# Pool_Interface_FEATHER-ESP8266.net
KiCad netlist of a schematic drawn in EAGLE
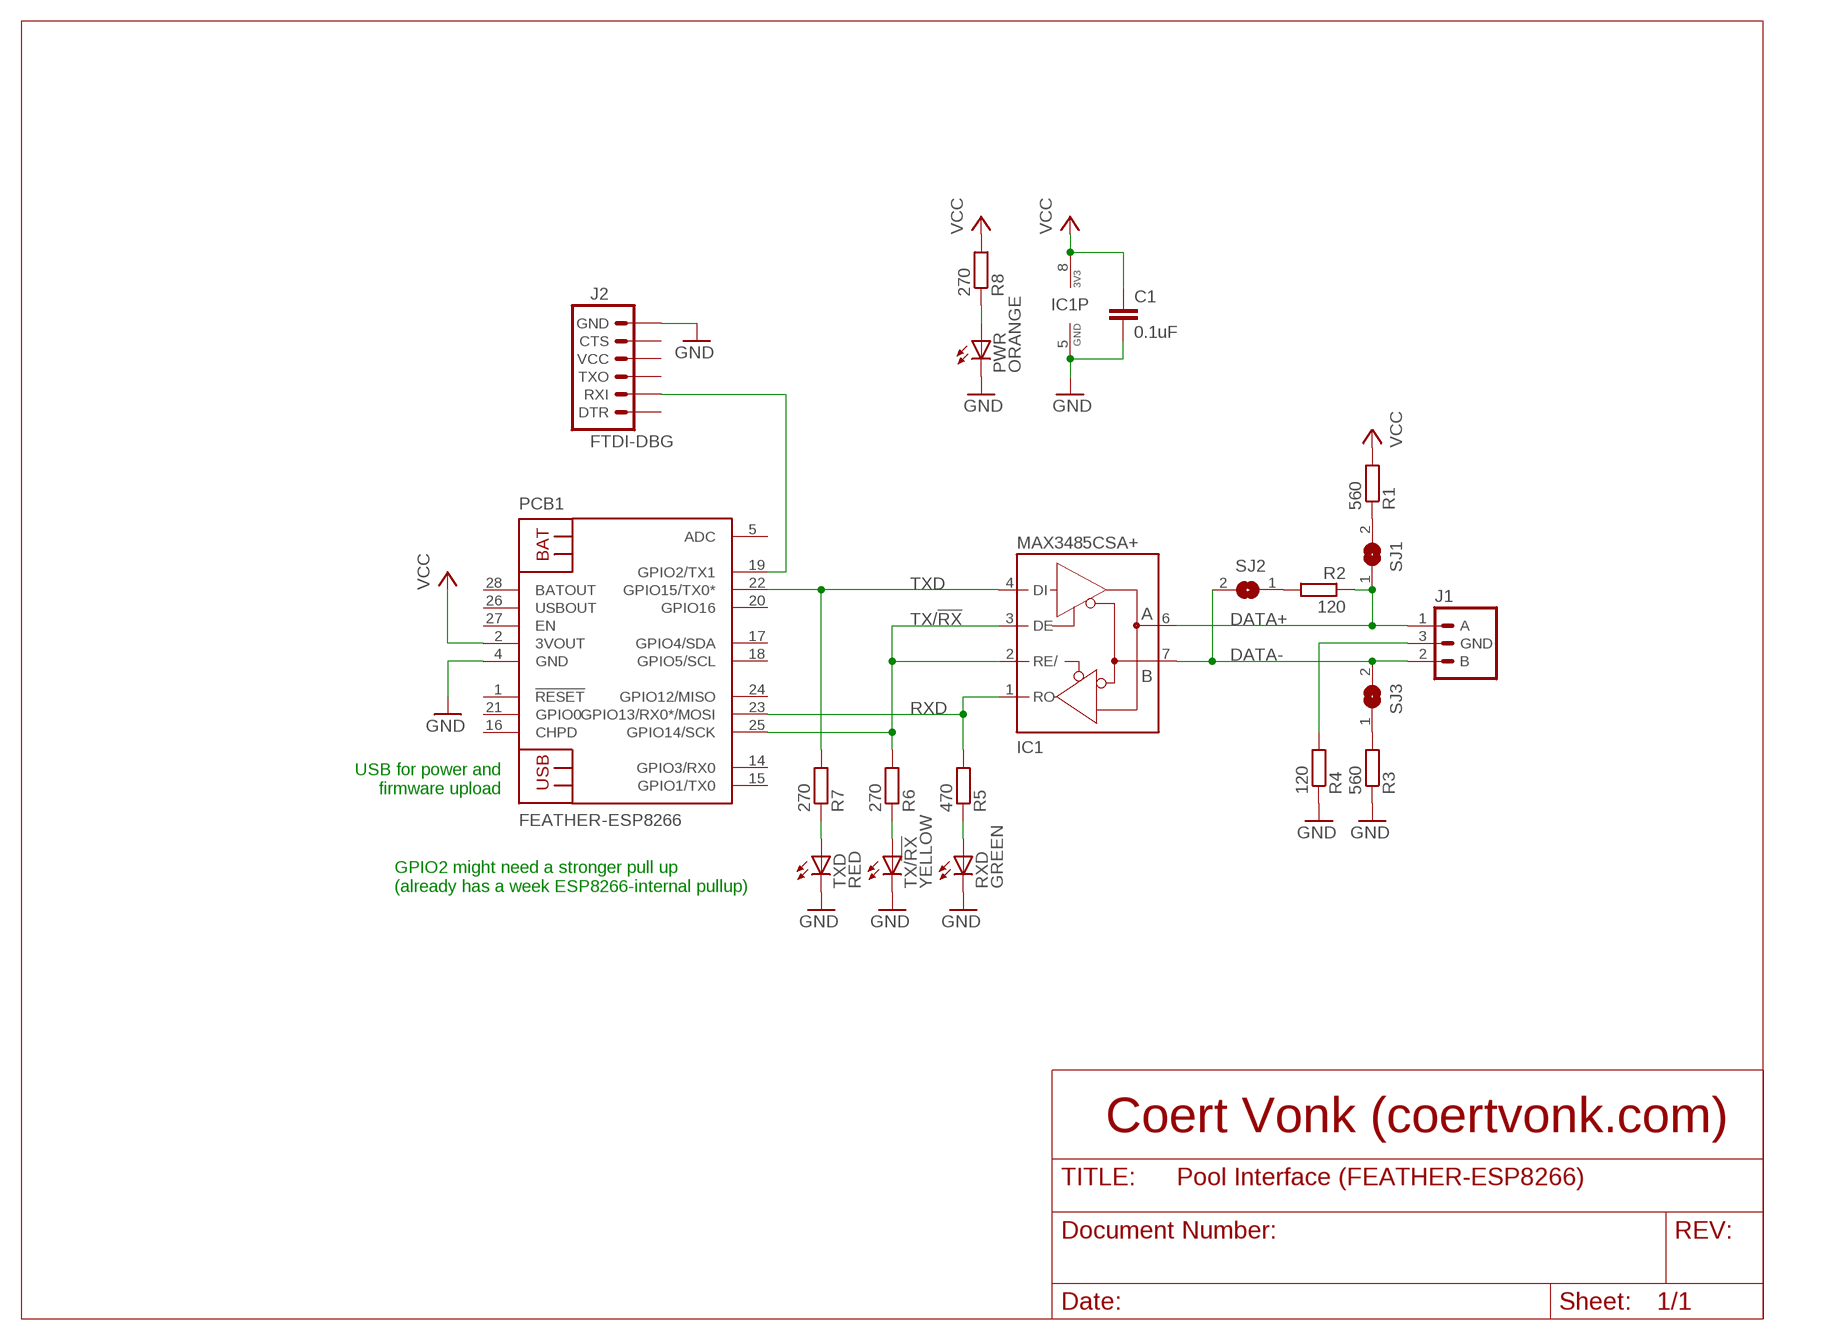
[diagram p0: schematic, sheet 1]

(export (version "E")
  (design (tool "Eeschema 10.0.6"))
  (components
    (comp (ref "C1")
      (value "0.1uF")
      (footprint "eagle-import:C0805K")
      (libsource (lib "eagle-import") (part "C-EUC0805K"))
    )
    (comp (ref "IC1")
      (value "MAX3485CSA+")
      (footprint "eagle-import:SO08")
      (fields (field (name "MF") "MAXIM") (field (name "MPN") "MAX481CSA"))
      (libsource (lib "eagle-import") (part "MAX3485CSA+"))
    )
    (comp (ref "J1")
      (value "RS485-CONSCREW")
      (footprint "eagle-import:SCREWTERMINAL-3.5MM-3")
      (libsource (lib "eagle-import") (part "RS485-CONSCREW"))
    )
    (comp (ref "J2")
      (value "FTDI-DBG")
      (footprint "eagle-import:1X06_LONGPADS")
      (libsource (lib "eagle-import") (part "ARDUINO_SERIAL_PROGRAMLONGPADS"))
    )
    (comp (ref "PCB1")
      (value "FEATHER-ESP8266")
      (footprint "eagle-import:FEATHER-ESP8266")
      (libsource (lib "eagle-import") (part "FEATHER-ESP8266"))
    )
    (comp (ref "PWR")
      (value "ORANGE")
      (footprint "eagle-import:SML0805")
      (libsource (lib "eagle-import") (part "LEDSML0805"))
    )
    (comp (ref "R1")
      (value "560")
      (footprint "eagle-import:R0805")
      (libsource (lib "eagle-import") (part "R-EU_R0805"))
    )
    (comp (ref "R2")
      (value "120")
      (footprint "eagle-import:R0805")
      (libsource (lib "eagle-import") (part "R-EU_R0805"))
    )
    (comp (ref "R3")
      (value "560")
      (footprint "eagle-import:R0805")
      (libsource (lib "eagle-import") (part "R-EU_R0805"))
    )
    (comp (ref "R4")
      (value "120")
      (footprint "eagle-import:R0805")
      (libsource (lib "eagle-import") (part "R-EU_R0805"))
    )
    (comp (ref "R5")
      (value "470")
      (footprint "eagle-import:R0805")
      (libsource (lib "eagle-import") (part "R-EU_R0805"))
    )
    (comp (ref "R6")
      (value "270")
      (footprint "eagle-import:R0805")
      (libsource (lib "eagle-import") (part "R-EU_R0805"))
    )
    (comp (ref "R7")
      (value "270")
      (footprint "eagle-import:R0805")
      (libsource (lib "eagle-import") (part "R-EU_R0805"))
    )
    (comp (ref "R8")
      (value "270")
      (footprint "eagle-import:R0805")
      (libsource (lib "eagle-import") (part "R-EU_R0805"))
    )
    (comp (ref "RXD")
      (value "GREEN")
      (footprint "eagle-import:SML0805")
      (libsource (lib "eagle-import") (part "LEDSML0805"))
    )
    (comp (ref "SJ1") (value "SJ") (footprint "eagle-import:SJ") (libsource (lib "eagle-import") (part "SJ")))
    (comp (ref "SJ2") (value "SJ") (footprint "eagle-import:SJ") (libsource (lib "eagle-import") (part "SJ")))
    (comp (ref "SJ3") (value "SJ") (footprint "eagle-import:SJ") (libsource (lib "eagle-import") (part "SJ")))
    (comp (ref "TX/!RX")
      (value "YELLOW")
      (footprint "eagle-import:SML0805")
      (libsource (lib "eagle-import") (part "LEDSML0805"))
    )
    (comp (ref "TXD")
      (value "RED")
      (footprint "eagle-import:SML0805")
      (libsource (lib "eagle-import") (part "LEDSML0805"))
    )
  )
  (nets
    (net (code "1") (name "/BATOUT") (class "Default")
      (node (ref "PCB1") (pin "28") (pinfunction "BATOUT_28") (pintype "power_in"))
    )
    (net (code "2") (name "/DATA+") (class "Default")
      (node (ref "IC1") (pin "6") (pinfunction "A_6") (pintype "passive"))
      (node (ref "J1") (pin "1") (pinfunction "A_1") (pintype "passive"))
      (node (ref "R2") (pin "1") (pinfunction "1_1") (pintype "passive"))
      (node (ref "SJ1") (pin "1") (pinfunction "1_1") (pintype "passive"))
    )
    (net (code "3") (name "/DATA-") (class "Default")
      (node (ref "IC1") (pin "7") (pinfunction "B_7") (pintype "passive"))
      (node (ref "J1") (pin "2") (pinfunction "B_2") (pintype "passive"))
      (node (ref "SJ2") (pin "2") (pinfunction "2_2") (pintype "passive"))
      (node (ref "SJ3") (pin "2") (pinfunction "2_2") (pintype "passive"))
    )
    (net (code "4") (name "/RXD") (class "Default")
      (node (ref "IC1") (pin "1") (pinfunction "RO_1") (pintype "output"))
      (node (ref "PCB1") (pin "23") (pinfunction "GPIO13/RX0*/MOSI_23") (pintype "bidirectional"))
      (node (ref "R5") (pin "2") (pinfunction "2_2") (pintype "passive"))
    )
    (net (code "5") (name "/TXD") (class "Default")
      (node (ref "IC1") (pin "4") (pinfunction "DI_4") (pintype "input"))
      (node (ref "PCB1") (pin "22") (pinfunction "GPIO15/TX0*_22") (pintype "bidirectional"))
      (node (ref "R7") (pin "2") (pinfunction "2_2") (pintype "passive"))
    )
    (net (code "6") (name "/TX{slash}~{RX}") (class "Default")
      (node (ref "IC1") (pin "2") (pinfunction "RE/_2") (pintype "input"))
      (node (ref "IC1") (pin "3") (pinfunction "DE_3") (pintype "input"))
      (node (ref "PCB1") (pin "25") (pinfunction "GPIO14/SCK_25") (pintype "bidirectional"))
      (node (ref "R6") (pin "2") (pinfunction "2_2") (pintype "passive"))
    )
    (net (code "7") (name "/USBOUT") (class "Default")
      (node (ref "PCB1") (pin "26") (pinfunction "USBOUT_26") (pintype "power_in"))
    )
    (net (code "8") (name "GND") (class "Default")
      (node (ref "C1") (pin "2") (pinfunction "2_2") (pintype "passive"))
      (node (ref "IC1") (pin "5") (pinfunction "GND_5") (pintype "power_in"))
      (node (ref "J2") (pin "6") (pinfunction "GND_6") (pintype "passive"))
      (node (ref "PCB1") (pin "4") (pinfunction "GND_4") (pintype "power_in"))
      (node (ref "PWR") (pin "C") (pinfunction "C_C") (pintype "passive"))
      (node (ref "R3") (pin "1") (pinfunction "1_1") (pintype "passive"))
      (node (ref "R4") (pin "1") (pinfunction "1_1") (pintype "passive"))
      (node (ref "RXD") (pin "C") (pinfunction "C_C") (pintype "passive"))
      (node (ref "TX/!RX") (pin "C") (pinfunction "C_C") (pintype "passive"))
      (node (ref "TXD") (pin "C") (pinfunction "C_C") (pintype "passive"))
    )
    (net (code "9") (name "Net-(J1-GND)") (class "Default")
      (node (ref "J1") (pin "3") (pinfunction "GND_3") (pintype "passive"))
      (node (ref "R4") (pin "2") (pinfunction "2_2") (pintype "passive"))
    )
    (net (code "10") (name "Net-(J2-RXI)") (class "Default")
      (node (ref "J2") (pin "2") (pinfunction "RXI_2") (pintype "passive"))
      (node (ref "PCB1") (pin "19") (pinfunction "GPIO2/TX1_19") (pintype "bidirectional"))
    )
    (net (code "11") (name "Net-(PWR-PadA)") (class "Default")
      (node (ref "PWR") (pin "A") (pinfunction "A_A") (pintype "passive"))
      (node (ref "R8") (pin "1") (pinfunction "1_1") (pintype "passive"))
    )
    (net (code "12") (name "Net-(R1-Pad1)") (class "Default")
      (node (ref "R1") (pin "1") (pinfunction "1_1") (pintype "passive"))
      (node (ref "SJ1") (pin "2") (pinfunction "2_2") (pintype "passive"))
    )
    (net (code "13") (name "Net-(R2-Pad2)") (class "Default")
      (node (ref "R2") (pin "2") (pinfunction "2_2") (pintype "passive"))
      (node (ref "SJ2") (pin "1") (pinfunction "1_1") (pintype "passive"))
    )
    (net (code "14") (name "Net-(R3-Pad2)") (class "Default")
      (node (ref "R3") (pin "2") (pinfunction "2_2") (pintype "passive"))
      (node (ref "SJ3") (pin "1") (pinfunction "1_1") (pintype "passive"))
    )
    (net (code "15") (name "Net-(R5-Pad1)") (class "Default")
      (node (ref "R5") (pin "1") (pinfunction "1_1") (pintype "passive"))
      (node (ref "RXD") (pin "A") (pinfunction "A_A") (pintype "passive"))
    )
    (net (code "16") (name "Net-(R6-Pad1)") (class "Default")
      (node (ref "R6") (pin "1") (pinfunction "1_1") (pintype "passive"))
      (node (ref "TX/!RX") (pin "A") (pinfunction "A_A") (pintype "passive"))
    )
    (net (code "17") (name "Net-(R7-Pad1)") (class "Default")
      (node (ref "R7") (pin "1") (pinfunction "1_1") (pintype "passive"))
      (node (ref "TXD") (pin "A") (pinfunction "A_A") (pintype "passive"))
    )
    (net (code "18") (name "VCC") (class "Default")
      (node (ref "C1") (pin "1") (pinfunction "1_1") (pintype "passive"))
      (node (ref "IC1") (pin "8") (pinfunction "5V_8") (pintype "power_in"))
      (node (ref "PCB1") (pin "2") (pinfunction "3VOUT_2") (pintype "power_in"))
      (node (ref "R1") (pin "2") (pinfunction "2_2") (pintype "passive"))
      (node (ref "R8") (pin "2") (pinfunction "2_2") (pintype "passive"))
    )
    (net (code "19") (name "unconnected-(J2-CTS-Pad5)") (class "Default")
      (node (ref "J2") (pin "5") (pinfunction "CTS_5") (pintype "passive"))
    )
    (net (code "20") (name "unconnected-(J2-DTR-Pad1)") (class "Default")
      (node (ref "J2") (pin "1") (pinfunction "DTR_1") (pintype "passive"))
    )
    (net (code "21") (name "unconnected-(J2-TXO-Pad3)") (class "Default")
      (node (ref "J2") (pin "3") (pinfunction "TXO_3") (pintype "passive"))
    )
    (net (code "22") (name "unconnected-(J2-VCC-Pad4)") (class "Default")
      (node (ref "J2") (pin "4") (pinfunction "VCC_4") (pintype "passive"))
    )
    (net (code "23") (name "unconnected-(PCB1-ADC-Pad5)") (class "Default")
      (node (ref "PCB1") (pin "5") (pinfunction "ADC_5") (pintype "bidirectional"))
    )
    (net (code "24") (name "unconnected-(PCB1-CHPD-Pad16)") (class "Default")
      (node (ref "PCB1") (pin "16") (pinfunction "CHPD_16") (pintype "passive"))
    )
    (net (code "25") (name "unconnected-(PCB1-EN-Pad27)") (class "Default")
      (node (ref "PCB1") (pin "27") (pinfunction "EN_27") (pintype "passive"))
    )
    (net (code "26") (name "unconnected-(PCB1-GPIO0-Pad21)") (class "Default")
      (node (ref "PCB1") (pin "21") (pinfunction "GPIO0_21") (pintype "bidirectional"))
    )
    (net (code "27") (name "unconnected-(PCB1-GPIO1{slash}TX0-Pad15)") (class "Default")
      (node (ref "PCB1") (pin "15") (pinfunction "GPIO1/TX0_15") (pintype "bidirectional"))
    )
    (net (code "28") (name "unconnected-(PCB1-GPIO3{slash}RX0-Pad14)") (class "Default")
      (node (ref "PCB1") (pin "14") (pinfunction "GPIO3/RX0_14") (pintype "bidirectional"))
    )
    (net (code "29") (name "unconnected-(PCB1-GPIO4{slash}SDA-Pad17)") (class "Default")
      (node (ref "PCB1") (pin "17") (pinfunction "GPIO4/SDA_17") (pintype "bidirectional"))
    )
    (net (code "30") (name "unconnected-(PCB1-GPIO5{slash}SCL-Pad18)") (class "Default")
      (node (ref "PCB1") (pin "18") (pinfunction "GPIO5/SCL_18") (pintype "bidirectional"))
    )
    (net (code "31") (name "unconnected-(PCB1-GPIO12{slash}MISO-Pad24)") (class "Default")
      (node (ref "PCB1") (pin "24") (pinfunction "GPIO12/MISO_24") (pintype "bidirectional"))
    )
    (net (code "32") (name "unconnected-(PCB1-GPIO16-Pad20)") (class "Default")
      (node (ref "PCB1") (pin "20") (pinfunction "GPIO16_20") (pintype "bidirectional"))
    )
    (net (code "33") (name "unconnected-(PCB1-~{RESET}-Pad1)") (class "Default")
      (node (ref "PCB1") (pin "1") (pinfunction "~{RESET}_1") (pintype "input"))
    )
  )
)
